# Dash_LEDs_r2.net
KiCad netlist of a schematic drawn in EAGLE
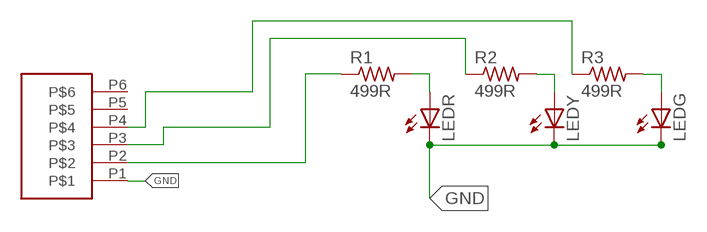
[diagram p0: schematic, sheet 1]

(export (version "E")
  (design (tool "Eeschema 10.0.6"))
  (components
    (comp (ref "LEDG")
      (value "LED5MM")
      (footprint "eagle-import:LED5MM")
      (libsource (lib "eagle-import") (part "LED5MM"))
    )
    (comp (ref "LEDR")
      (value "LED5MM")
      (footprint "eagle-import:LED5MM")
      (libsource (lib "eagle-import") (part "LED5MM"))
    )
    (comp (ref "LEDY")
      (value "LED5MM")
      (footprint "eagle-import:LED5MM")
      (libsource (lib "eagle-import") (part "LED5MM"))
    )
    (comp (ref "R1")
      (value "499R")
      (footprint "eagle-import:R0805")
      (libsource (lib "eagle-import") (part "R-US_R0805"))
    )
    (comp (ref "R2")
      (value "499R")
      (footprint "eagle-import:R0805")
      (libsource (lib "eagle-import") (part "R-US_R0805"))
    )
    (comp (ref "R3")
      (value "499R")
      (footprint "eagle-import:R0805")
      (libsource (lib "eagle-import") (part "R-US_R0805"))
    )
    (comp (ref "U$1")
      (value "MICRO6LOCK")
      (footprint "eagle-import:MICRO6LOCK")
      (libsource (lib "eagle-import") (part "MICRO6LOCK"))
    )
  )
  (nets
    (net (code "1") (name "GND") (class "Default")
      (node (ref "LEDG") (pin "K") (pinfunction "C_K") (pintype "passive"))
      (node (ref "LEDR") (pin "K") (pinfunction "C_K") (pintype "passive"))
      (node (ref "LEDY") (pin "K") (pinfunction "C_K") (pintype "passive"))
      (node (ref "U$1") (pin "P1") (pinfunction "P$1_P1") (pintype "bidirectional"))
    )
    (net (code "2") (name "Net-(LEDG-PadA)") (class "Default")
      (node (ref "LEDG") (pin "A") (pinfunction "A_A") (pintype "passive"))
      (node (ref "R3") (pin "2") (pinfunction "2_2") (pintype "passive"))
    )
    (net (code "3") (name "Net-(LEDR-PadA)") (class "Default")
      (node (ref "LEDR") (pin "A") (pinfunction "A_A") (pintype "passive"))
      (node (ref "R1") (pin "2") (pinfunction "2_2") (pintype "passive"))
    )
    (net (code "4") (name "Net-(LEDY-PadA)") (class "Default")
      (node (ref "LEDY") (pin "A") (pinfunction "A_A") (pintype "passive"))
      (node (ref "R2") (pin "2") (pinfunction "2_2") (pintype "passive"))
    )
    (net (code "5") (name "Net-(U$1-P$2)") (class "Default")
      (node (ref "R1") (pin "1") (pinfunction "1_1") (pintype "passive"))
      (node (ref "U$1") (pin "P2") (pinfunction "P$2_P2") (pintype "bidirectional"))
    )
    (net (code "6") (name "Net-(U$1-P$3)") (class "Default")
      (node (ref "R2") (pin "1") (pinfunction "1_1") (pintype "passive"))
      (node (ref "U$1") (pin "P3") (pinfunction "P$3_P3") (pintype "bidirectional"))
    )
    (net (code "7") (name "Net-(U$1-P$4)") (class "Default")
      (node (ref "R3") (pin "1") (pinfunction "1_1") (pintype "passive"))
      (node (ref "U$1") (pin "P4") (pinfunction "P$4_P4") (pintype "bidirectional"))
    )
    (net (code "8") (name "unconnected-(U$1-P$5-PadP5)") (class "Default")
      (node (ref "U$1") (pin "P5") (pinfunction "P$5_P5") (pintype "bidirectional"))
    )
    (net (code "9") (name "unconnected-(U$1-P$6-PadP6)") (class "Default")
      (node (ref "U$1") (pin "P6") (pinfunction "P$6_P6") (pintype "bidirectional"))
    )
  )
)
